# GNUBLIN-DIP-EASY_V100.net
KiCad netlist of a schematic drawn in EAGLE
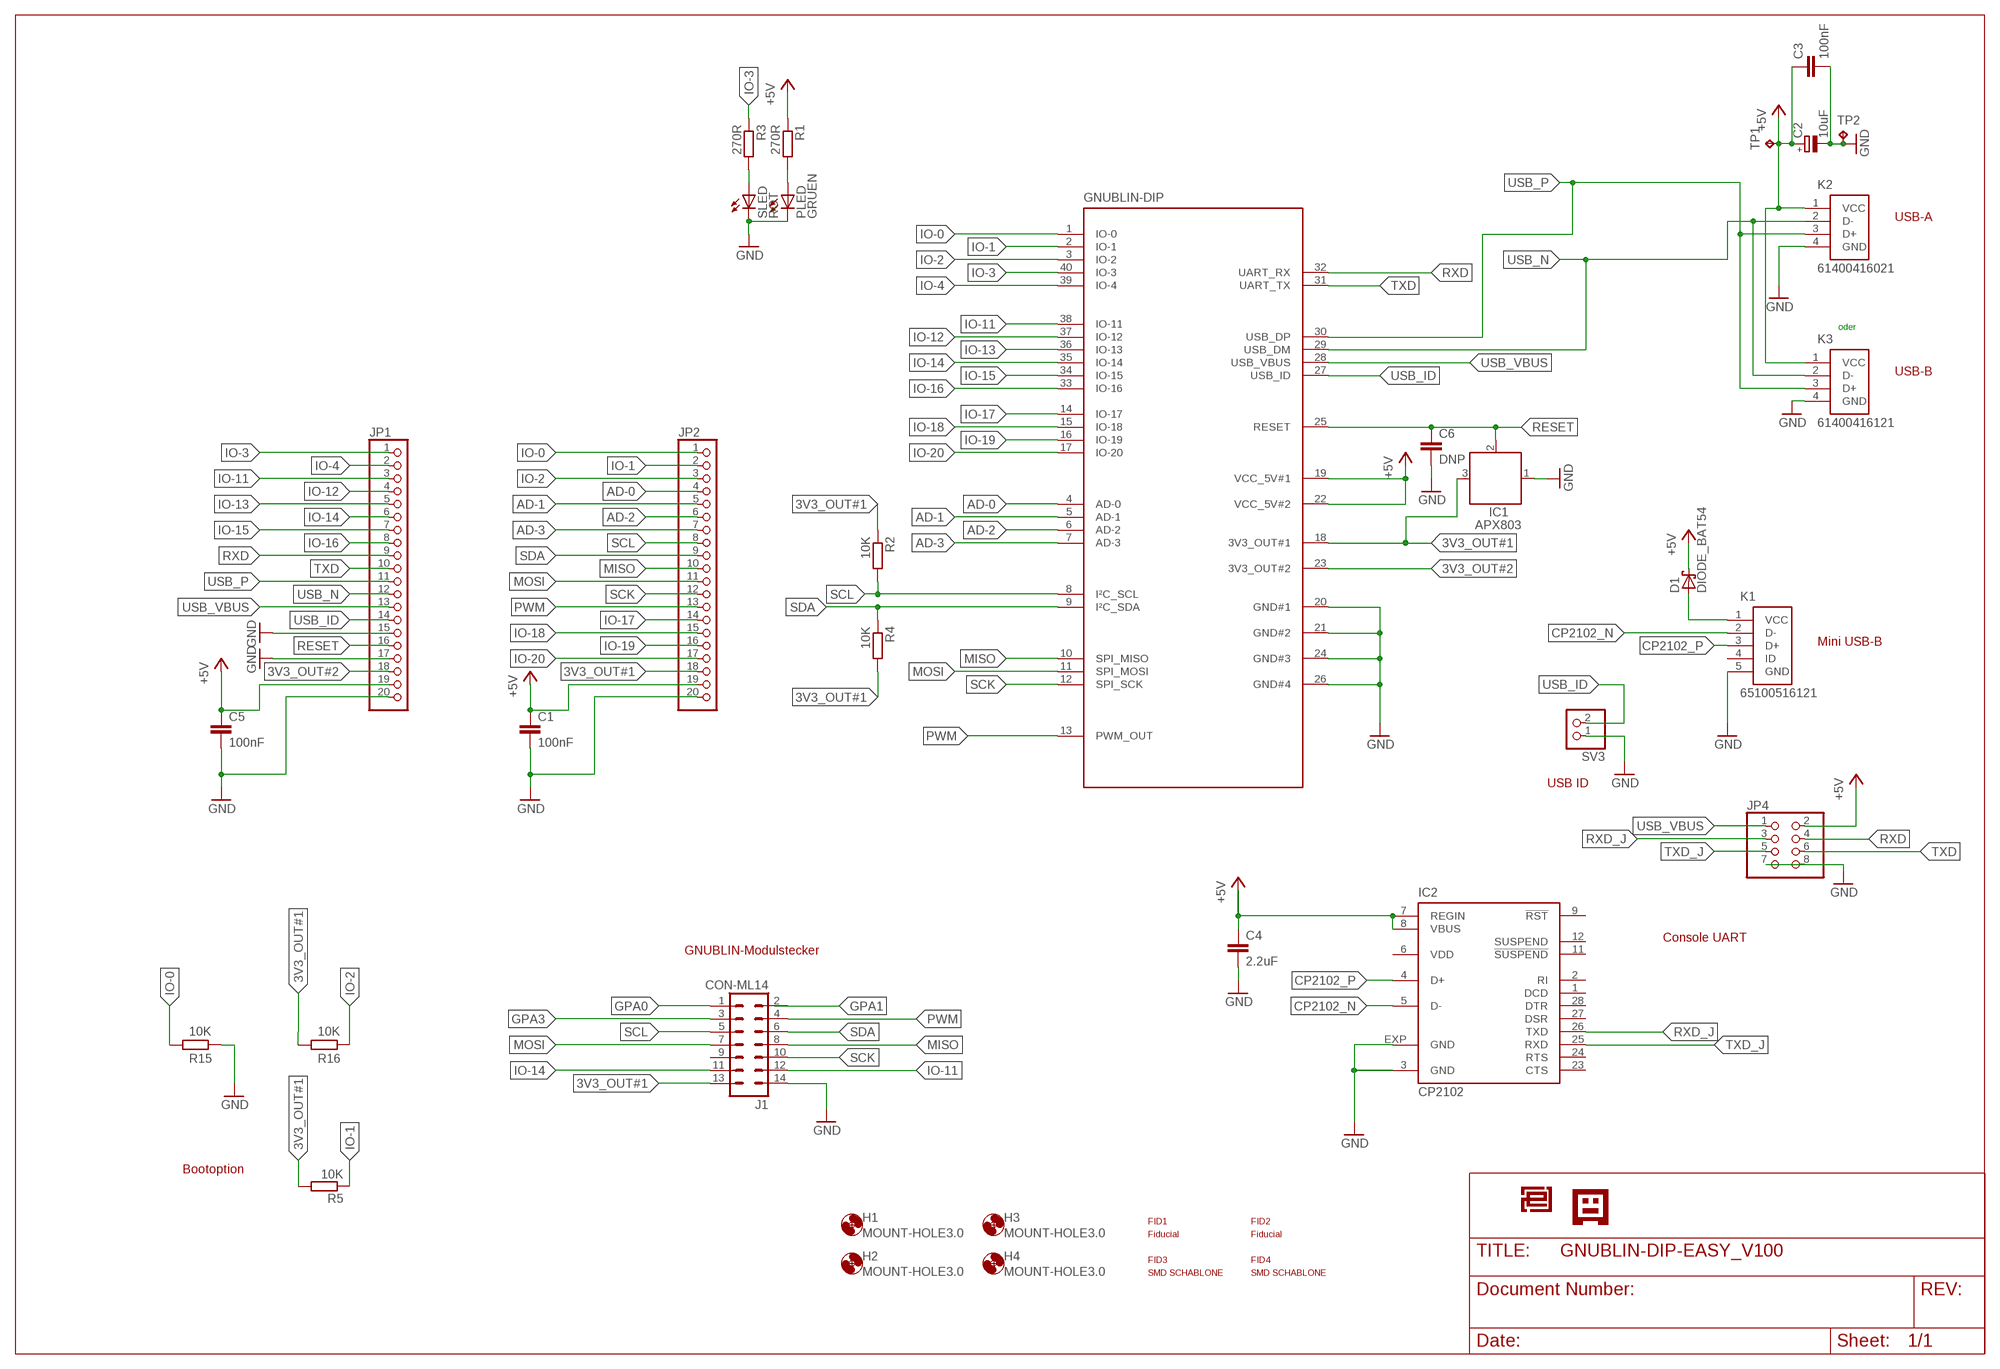
[diagram p0: schematic, sheet 1]

(export (version "E")
  (design (tool "Eeschema 10.0.6"))
  (components
    (comp (ref "C1")
      (value "100nF")
      (footprint "eagle-import:C0805")
      (libsource (lib "eagle-import") (part "C-EUC0805"))
    )
    (comp (ref "C2")
      (value "10uF")
      (footprint "eagle-import:D_7343-31R")
      (libsource (lib "eagle-import") (part "CPOL-EUD/7343-31R"))
    )
    (comp (ref "C3")
      (value "100nF")
      (footprint "eagle-import:C0805")
      (libsource (lib "eagle-import") (part "C-EUC0805"))
    )
    (comp (ref "C4")
      (value "2.2uF")
      (footprint "eagle-import:C0805")
      (libsource (lib "eagle-import") (part "C-EUC0805"))
    )
    (comp (ref "C5")
      (value "100nF")
      (footprint "eagle-import:C0805")
      (libsource (lib "eagle-import") (part "C-EUC0805"))
    )
    (comp (ref "C6")
      (value "DNP")
      (footprint "eagle-import:C0805")
      (libsource (lib "eagle-import") (part "C-EUC0805"))
    )
    (comp (ref "D1")
      (value "DIODE_BAT54")
      (footprint "eagle-import:SOT-23")
      (libsource (lib "eagle-import") (part "DIODE_BAT54"))
    )
    (comp (ref "FID1")
      (value "PASSERMARKEN_FIDUCIAL")
      (footprint "eagle-import:PASSERMARKEN_FIDUCIAL")
      (libsource (lib "eagle-import") (part "PASSERMARKEN_FIDUCIAL"))
    )
    (comp (ref "FID2")
      (value "PASSERMARKEN_FIDUCIAL")
      (footprint "eagle-import:PASSERMARKEN_FIDUCIAL")
      (libsource (lib "eagle-import") (part "PASSERMARKEN_FIDUCIAL"))
    )
    (comp (ref "FID3")
      (value "PASSERMARKEN_FIDUCIAL")
      (footprint "eagle-import:PASSERMARKEN_FIDUCIAL")
      (libsource (lib "eagle-import") (part "SMDSCHABLONE_PASSERMARKEN_FIDUCIAL"))
    )
    (comp (ref "FID4")
      (value "PASSERMARKEN_FIDUCIAL")
      (footprint "eagle-import:PASSERMARKEN_FIDUCIAL")
      (libsource (lib "eagle-import") (part "SMDSCHABLONE_PASSERMARKEN_FIDUCIAL"))
    )
    (comp (ref "H1")
      (value "MOUNT-HOLE3.0")
      (footprint "eagle-import:3,0")
      (libsource (lib "eagle-import") (part "MOUNT-HOLE3.0"))
    )
    (comp (ref "H2")
      (value "MOUNT-HOLE3.0")
      (footprint "eagle-import:3,0")
      (libsource (lib "eagle-import") (part "MOUNT-HOLE3.0"))
    )
    (comp (ref "H3")
      (value "MOUNT-HOLE3.0")
      (footprint "eagle-import:3,0")
      (libsource (lib "eagle-import") (part "MOUNT-HOLE3.0"))
    )
    (comp (ref "H4")
      (value "MOUNT-HOLE3.0")
      (footprint "eagle-import:3,0")
      (libsource (lib "eagle-import") (part "MOUNT-HOLE3.0"))
    )
    (comp (ref "IC1")
      (value "APX803")
      (footprint "eagle-import:SOT23")
      (libsource (lib "eagle-import") (part "APX803"))
    )
    (comp (ref "IC2")
      (value "CP2102")
      (footprint "eagle-import:MLP28")
      (fields (field (name "MF") "FARNELL") (field (name "MPN") "CP2102-GM"))
      (libsource (lib "eagle-import") (part "CP2102"))
    )
    (comp (ref "J1")
      (value "CON-ML14")
      (footprint "eagle-import:ML-14")
      (libsource (lib "eagle-import") (part "CON-ML14"))
    )
    (comp (ref "JP1")
      (value "PINHD-1X20")
      (footprint "eagle-import:1X20")
      (libsource (lib "eagle-import") (part "PINHD-1X20"))
    )
    (comp (ref "JP2")
      (value "PINHD-1X20")
      (footprint "eagle-import:1X20")
      (libsource (lib "eagle-import") (part "PINHD-1X20"))
    )
    (comp (ref "JP4")
      (value "PINHD-2X4")
      (footprint "eagle-import:2X04")
      (libsource (lib "eagle-import") (part "PINHD-2X4"))
    )
    (comp (ref "K1")
      (value "65100516121")
      (footprint "eagle-import:65100516121")
      (libsource (lib "eagle-import") (part "65100516121"))
    )
    (comp (ref "K2")
      (value "61400416021")
      (footprint "eagle-import:61400416021")
      (libsource (lib "eagle-import") (part "61400416021"))
    )
    (comp (ref "K3")
      (value "61400416121")
      (footprint "eagle-import:61400416121")
      (libsource (lib "eagle-import") (part "61400416121"))
    )
    (comp (ref "PLED")
      (value "GRUEN")
      (footprint "eagle-import:CHIPLED_0805")
      (libsource (lib "eagle-import") (part "LEDCHIPLED_0805"))
    )
    (comp (ref "R1")
      (value "270R")
      (footprint "eagle-import:R0805")
      (libsource (lib "eagle-import") (part "R-EU_R0805"))
    )
    (comp (ref "R2")
      (value "10K")
      (footprint "eagle-import:R0805")
      (libsource (lib "eagle-import") (part "R-EU_R0805"))
    )
    (comp (ref "R3")
      (value "270R")
      (footprint "eagle-import:R0805")
      (libsource (lib "eagle-import") (part "R-EU_R0805"))
    )
    (comp (ref "R4")
      (value "10K")
      (footprint "eagle-import:R0805")
      (libsource (lib "eagle-import") (part "R-EU_R0805"))
    )
    (comp (ref "R5")
      (value "10K")
      (footprint "eagle-import:R0805")
      (libsource (lib "eagle-import") (part "R-EU_R0805"))
    )
    (comp (ref "R15")
      (value "10K")
      (footprint "eagle-import:R0805")
      (libsource (lib "eagle-import") (part "R-EU_R0805"))
    )
    (comp (ref "R16")
      (value "10K")
      (footprint "eagle-import:R0805")
      (libsource (lib "eagle-import") (part "R-EU_R0805"))
    )
    (comp (ref "SLED")
      (value "ROT")
      (footprint "eagle-import:CHIPLED_0805")
      (libsource (lib "eagle-import") (part "LEDCHIPLED_0805"))
    )
    (comp (ref "SV3")
      (value "PINHD-1X2")
      (footprint "eagle-import:1X02")
      (libsource (lib "eagle-import") (part "PINHD-1X2"))
    )
    (comp (ref "TP1")
      (value "TPB1,27")
      (footprint "eagle-import:B1,27")
      (libsource (lib "eagle-import") (part "TPB1,27"))
    )
    (comp (ref "TP2")
      (value "TPB1,27")
      (footprint "eagle-import:B1,27")
      (libsource (lib "eagle-import") (part "TPB1,27"))
    )
    (comp (ref "U$1")
      (value "GNUBLIN-LOGODRUCK")
      (footprint "eagle-import:GNUBLINSIEBDRUCK")
      (libsource (lib "eagle-import") (part "GNUBLIN-LOGODRUCK"))
    )
    (comp (ref "U$2")
      (value "EPLOGOSIEB")
      (footprint "eagle-import:EPLOGOSIEBDRUCK")
      (libsource (lib "eagle-import") (part "EPLOGOSIEB"))
    )
    (comp (ref "U4")
      (value "GNUBLIN-DIP")
      (footprint "eagle-import:DIL40")
      (libsource (lib "eagle-import") (part "GNUBLIN-DIP"))
    )
  )
  (nets
    (net (code "1") (name "+5V") (class "Default")
      (node (ref "C1") (pin "1") (pinfunction "1_1") (pintype "passive"))
      (node (ref "C2") (pin "+") (pinfunction "+_+") (pintype "passive"))
      (node (ref "C3") (pin "1") (pinfunction "1_1") (pintype "passive"))
      (node (ref "C4") (pin "1") (pinfunction "1_1") (pintype "passive"))
      (node (ref "C5") (pin "1") (pinfunction "1_1") (pintype "passive"))
      (node (ref "D1") (pin "3") (pinfunction "C_3") (pintype "passive"))
      (node (ref "IC2") (pin "7") (pinfunction "REGIN_7") (pintype "passive"))
      (node (ref "IC2") (pin "8") (pinfunction "VBUS_8") (pintype "input"))
      (node (ref "JP1") (pin "19") (pinfunction "19_19") (pintype "passive"))
      (node (ref "JP2") (pin "19") (pinfunction "19_19") (pintype "passive"))
      (node (ref "JP4") (pin "2") (pinfunction "2_2") (pintype "passive"))
      (node (ref "K2") (pin "1") (pinfunction "VCC_1") (pintype "passive"))
      (node (ref "K3") (pin "1") (pinfunction "VCC_1") (pintype "passive"))
      (node (ref "R1") (pin "1") (pinfunction "1_1") (pintype "passive"))
      (node (ref "TP1") (pin "TP") (pinfunction "TP_TP") (pintype "input"))
      (node (ref "U4") (pin "19") (pinfunction "VCC_5V#1_19") (pintype "power_in"))
      (node (ref "U4") (pin "22") (pinfunction "VCC_5V#2_22") (pintype "power_in"))
    )
    (net (code "2") (name "/VDD") (class "Default")
      (node (ref "IC2") (pin "6") (pinfunction "VDD_6") (pintype "power_in"))
    )
    (net (code "3") (name "3V3_OUT#1") (class "Default")
      (node (ref "IC1") (pin "3") (pinfunction "VCC_3") (pintype "power_in"))
      (node (ref "J1") (pin "13") (pinfunction "13_13") (pintype "passive"))
      (node (ref "JP2") (pin "18") (pinfunction "18_18") (pintype "passive"))
      (node (ref "R16") (pin "1") (pinfunction "1_1") (pintype "passive"))
      (node (ref "R2") (pin "1") (pinfunction "1_1") (pintype "passive"))
      (node (ref "R4") (pin "2") (pinfunction "2_2") (pintype "passive"))
      (node (ref "R5") (pin "2") (pinfunction "2_2") (pintype "passive"))
      (node (ref "U4") (pin "18") (pinfunction "3V3_OUT#1_18") (pintype "power_in"))
    )
    (net (code "4") (name "3V3_OUT#2") (class "Default")
      (node (ref "JP1") (pin "18") (pinfunction "18_18") (pintype "passive"))
      (node (ref "U4") (pin "23") (pinfunction "3V3_OUT#2_23") (pintype "power_in"))
    )
    (net (code "5") (name "AD-0") (class "Default")
      (node (ref "JP2") (pin "4") (pinfunction "4_4") (pintype "passive"))
      (node (ref "U4") (pin "4") (pinfunction "AD-0_4") (pintype "input"))
    )
    (net (code "6") (name "AD-1") (class "Default")
      (node (ref "JP2") (pin "5") (pinfunction "5_5") (pintype "passive"))
      (node (ref "U4") (pin "5") (pinfunction "AD-1_5") (pintype "input"))
    )
    (net (code "7") (name "AD-2") (class "Default")
      (node (ref "JP2") (pin "6") (pinfunction "6_6") (pintype "passive"))
      (node (ref "U4") (pin "6") (pinfunction "AD-2_6") (pintype "input"))
    )
    (net (code "8") (name "AD-3") (class "Default")
      (node (ref "JP2") (pin "7") (pinfunction "7_7") (pintype "passive"))
      (node (ref "U4") (pin "7") (pinfunction "AD-3_7") (pintype "input"))
    )
    (net (code "9") (name "CP2102_N") (class "Default")
      (node (ref "IC2") (pin "5") (pinfunction "D-_5") (pintype "bidirectional"))
      (node (ref "K1") (pin "2") (pinfunction "D-_2") (pintype "passive"))
    )
    (net (code "10") (name "CP2102_P") (class "Default")
      (node (ref "IC2") (pin "4") (pinfunction "D+_4") (pintype "bidirectional"))
      (node (ref "K1") (pin "3") (pinfunction "D+_3") (pintype "passive"))
    )
    (net (code "11") (name "GND") (class "Default")
      (node (ref "C1") (pin "2") (pinfunction "2_2") (pintype "passive"))
      (node (ref "C2") (pin "-") (pinfunction "-_-") (pintype "passive"))
      (node (ref "C3") (pin "2") (pinfunction "2_2") (pintype "passive"))
      (node (ref "C4") (pin "2") (pinfunction "2_2") (pintype "passive"))
      (node (ref "C5") (pin "2") (pinfunction "2_2") (pintype "passive"))
      (node (ref "C6") (pin "2") (pinfunction "2_2") (pintype "passive"))
      (node (ref "IC1") (pin "1") (pinfunction "GND_1") (pintype "power_in"))
      (node (ref "IC2") (pin "3") (pinfunction "GND_3") (pintype "power_in"))
      (node (ref "IC2") (pin "EXP") (pinfunction "GND_EXP") (pintype "bidirectional"))
      (node (ref "J1") (pin "14") (pinfunction "14_14") (pintype "passive"))
      (node (ref "JP1") (pin "15") (pinfunction "15_15") (pintype "passive"))
      (node (ref "JP1") (pin "17") (pinfunction "17_17") (pintype "passive"))
      (node (ref "JP1") (pin "20") (pinfunction "20_20") (pintype "passive"))
      (node (ref "JP2") (pin "20") (pinfunction "20_20") (pintype "passive"))
      (node (ref "JP4") (pin "7") (pinfunction "7_7") (pintype "passive"))
      (node (ref "JP4") (pin "8") (pinfunction "8_8") (pintype "passive"))
      (node (ref "K1") (pin "5") (pinfunction "GND_5") (pintype "passive"))
      (node (ref "K2") (pin "4") (pinfunction "GND_4") (pintype "passive"))
      (node (ref "K3") (pin "4") (pinfunction "GND_4") (pintype "passive"))
      (node (ref "PLED") (pin "C") (pinfunction "C_C") (pintype "passive"))
      (node (ref "R15") (pin "2") (pinfunction "2_2") (pintype "passive"))
      (node (ref "SLED") (pin "C") (pinfunction "C_C") (pintype "passive"))
      (node (ref "SV3") (pin "1") (pinfunction "1_1") (pintype "passive"))
      (node (ref "TP2") (pin "TP") (pinfunction "TP_TP") (pintype "input"))
      (node (ref "U4") (pin "20") (pinfunction "GND#1_20") (pintype "power_in"))
      (node (ref "U4") (pin "21") (pinfunction "GND#2_21") (pintype "power_in"))
      (node (ref "U4") (pin "24") (pinfunction "GND#3_24") (pintype "power_in"))
      (node (ref "U4") (pin "26") (pinfunction "GND#4_26") (pintype "power_in"))
    )
    (net (code "12") (name "GPA0") (class "Default")
      (node (ref "J1") (pin "1") (pinfunction "1_1") (pintype "passive"))
    )
    (net (code "14") (name "GPA3") (class "Default")
      (node (ref "J1") (pin "3") (pinfunction "3_3") (pintype "passive"))
    )
    (net (code "15") (name "IO-0") (class "Default")
      (node (ref "JP2") (pin "1") (pinfunction "1_1") (pintype "passive"))
      (node (ref "R15") (pin "1") (pinfunction "1_1") (pintype "passive"))
      (node (ref "U4") (pin "1") (pinfunction "IO-0_1") (pintype "bidirectional"))
    )
    (net (code "16") (name "IO-1") (class "Default")
      (node (ref "JP2") (pin "2") (pinfunction "2_2") (pintype "passive"))
      (node (ref "R5") (pin "1") (pinfunction "1_1") (pintype "passive"))
      (node (ref "U4") (pin "2") (pinfunction "IO-1_2") (pintype "bidirectional"))
    )
    (net (code "17") (name "IO-2") (class "Default")
      (node (ref "JP2") (pin "3") (pinfunction "3_3") (pintype "passive"))
      (node (ref "R16") (pin "2") (pinfunction "2_2") (pintype "passive"))
      (node (ref "U4") (pin "3") (pinfunction "IO-2_3") (pintype "bidirectional"))
    )
    (net (code "18") (name "IO-3") (class "Default")
      (node (ref "JP1") (pin "1") (pinfunction "1_1") (pintype "passive"))
      (node (ref "R3") (pin "1") (pinfunction "1_1") (pintype "passive"))
      (node (ref "U4") (pin "40") (pinfunction "IO-3_40") (pintype "bidirectional"))
    )
    (net (code "19") (name "IO-4") (class "Default")
      (node (ref "JP1") (pin "2") (pinfunction "2_2") (pintype "passive"))
      (node (ref "U4") (pin "39") (pinfunction "IO-4_39") (pintype "bidirectional"))
    )
    (net (code "20") (name "IO-11") (class "Default")
      (node (ref "J1") (pin "12") (pinfunction "12_12") (pintype "passive"))
      (node (ref "JP1") (pin "3") (pinfunction "3_3") (pintype "passive"))
      (node (ref "U4") (pin "38") (pinfunction "IO-11_38") (pintype "bidirectional"))
    )
    (net (code "21") (name "IO-12") (class "Default")
      (node (ref "JP1") (pin "4") (pinfunction "4_4") (pintype "passive"))
      (node (ref "U4") (pin "37") (pinfunction "IO-12_37") (pintype "bidirectional"))
    )
    (net (code "22") (name "IO-13") (class "Default")
      (node (ref "JP1") (pin "5") (pinfunction "5_5") (pintype "passive"))
      (node (ref "U4") (pin "36") (pinfunction "IO-13_36") (pintype "bidirectional"))
    )
    (net (code "23") (name "IO-14") (class "Default")
      (node (ref "J1") (pin "11") (pinfunction "11_11") (pintype "passive"))
      (node (ref "JP1") (pin "6") (pinfunction "6_6") (pintype "passive"))
      (node (ref "U4") (pin "35") (pinfunction "IO-14_35") (pintype "bidirectional"))
    )
    (net (code "24") (name "IO-15") (class "Default")
      (node (ref "JP1") (pin "7") (pinfunction "7_7") (pintype "passive"))
      (node (ref "U4") (pin "34") (pinfunction "IO-15_34") (pintype "bidirectional"))
    )
    (net (code "25") (name "IO-16") (class "Default")
      (node (ref "JP1") (pin "8") (pinfunction "8_8") (pintype "passive"))
      (node (ref "U4") (pin "33") (pinfunction "IO-16_33") (pintype "bidirectional"))
    )
    (net (code "26") (name "IO-17") (class "Default")
      (node (ref "JP2") (pin "14") (pinfunction "14_14") (pintype "passive"))
      (node (ref "U4") (pin "14") (pinfunction "IO-17_14") (pintype "bidirectional"))
    )
    (net (code "27") (name "IO-18") (class "Default")
      (node (ref "JP2") (pin "15") (pinfunction "15_15") (pintype "passive"))
      (node (ref "U4") (pin "15") (pinfunction "IO-18_15") (pintype "bidirectional"))
    )
    (net (code "28") (name "IO-19") (class "Default")
      (node (ref "JP2") (pin "16") (pinfunction "16_16") (pintype "passive"))
      (node (ref "U4") (pin "16") (pinfunction "IO-19_16") (pintype "bidirectional"))
    )
    (net (code "29") (name "IO-20") (class "Default")
      (node (ref "JP2") (pin "17") (pinfunction "17_17") (pintype "passive"))
      (node (ref "U4") (pin "17") (pinfunction "IO-20_17") (pintype "bidirectional"))
    )
    (net (code "30") (name "MISO") (class "Default")
      (node (ref "J1") (pin "8") (pinfunction "8_8") (pintype "passive"))
      (node (ref "JP2") (pin "10") (pinfunction "10_10") (pintype "passive"))
      (node (ref "U4") (pin "10") (pinfunction "SPI_MISO_10") (pintype "bidirectional"))
    )
    (net (code "31") (name "MOSI") (class "Default")
      (node (ref "J1") (pin "7") (pinfunction "7_7") (pintype "passive"))
      (node (ref "JP2") (pin "11") (pinfunction "11_11") (pintype "passive"))
      (node (ref "U4") (pin "11") (pinfunction "SPI_MOSI_11") (pintype "bidirectional"))
    )
    (net (code "32") (name "Net-(D1-A)") (class "Default")
      (node (ref "D1") (pin "1") (pinfunction "A_1") (pintype "passive"))
      (node (ref "K1") (pin "1") (pinfunction "VCC_1") (pintype "passive"))
    )
    (net (code "33") (name "Net-(PLED-PadA)") (class "Default")
      (node (ref "PLED") (pin "A") (pinfunction "A_A") (pintype "passive"))
      (node (ref "R1") (pin "2") (pinfunction "2_2") (pintype "passive"))
    )
    (net (code "34") (name "Net-(R3-Pad2)") (class "Default")
      (node (ref "R3") (pin "2") (pinfunction "2_2") (pintype "passive"))
      (node (ref "SLED") (pin "A") (pinfunction "A_A") (pintype "passive"))
    )
    (net (code "35") (name "PWM") (class "Default")
      (node (ref "J1") (pin "4") (pinfunction "4_4") (pintype "passive"))
      (node (ref "JP2") (pin "13") (pinfunction "13_13") (pintype "passive"))
      (node (ref "U4") (pin "13") (pinfunction "PWM_OUT_13") (pintype "output"))
    )
    (net (code "36") (name "RESET") (class "Default")
      (node (ref "C6") (pin "1") (pinfunction "1_1") (pintype "passive"))
      (node (ref "IC1") (pin "2") (pinfunction "~{RESET}_2") (pintype "output"))
      (node (ref "JP1") (pin "16") (pinfunction "16_16") (pintype "passive"))
      (node (ref "U4") (pin "25") (pinfunction "RESET_25") (pintype "input"))
    )
    (net (code "37") (name "RXD") (class "Default")
      (node (ref "JP1") (pin "9") (pinfunction "9_9") (pintype "passive"))
      (node (ref "JP4") (pin "4") (pinfunction "4_4") (pintype "passive"))
      (node (ref "U4") (pin "32") (pinfunction "UART_RX_32") (pintype "input"))
    )
    (net (code "38") (name "RXD_J") (class "Default")
      (node (ref "IC2") (pin "26") (pinfunction "TXD_26") (pintype "output"))
      (node (ref "JP4") (pin "3") (pinfunction "3_3") (pintype "passive"))
    )
    (net (code "39") (name "SCK") (class "Default")
      (node (ref "J1") (pin "10") (pinfunction "10_10") (pintype "passive"))
      (node (ref "JP2") (pin "12") (pinfunction "12_12") (pintype "passive"))
      (node (ref "U4") (pin "12") (pinfunction "SPI_SCK_12") (pintype "bidirectional"))
    )
    (net (code "40") (name "SCL") (class "Default")
      (node (ref "J1") (pin "5") (pinfunction "5_5") (pintype "passive"))
      (node (ref "JP2") (pin "8") (pinfunction "8_8") (pintype "passive"))
      (node (ref "R2") (pin "2") (pinfunction "2_2") (pintype "passive"))
      (node (ref "U4") (pin "8") (pinfunction "I²C_SCL_8") (pintype "bidirectional"))
    )
    (net (code "41") (name "SDA") (class "Default")
      (node (ref "J1") (pin "6") (pinfunction "6_6") (pintype "passive"))
      (node (ref "JP2") (pin "9") (pinfunction "9_9") (pintype "passive"))
      (node (ref "R4") (pin "1") (pinfunction "1_1") (pintype "passive"))
      (node (ref "U4") (pin "9") (pinfunction "I²C_SDA_9") (pintype "bidirectional"))
    )
    (net (code "42") (name "TXD") (class "Default")
      (node (ref "JP1") (pin "10") (pinfunction "10_10") (pintype "passive"))
      (node (ref "JP4") (pin "6") (pinfunction "6_6") (pintype "passive"))
      (node (ref "U4") (pin "31") (pinfunction "UART_TX_31") (pintype "output"))
    )
    (net (code "43") (name "TXD_J") (class "Default")
      (node (ref "IC2") (pin "25") (pinfunction "RXD_25") (pintype "input"))
      (node (ref "JP4") (pin "5") (pinfunction "5_5") (pintype "passive"))
    )
    (net (code "44") (name "USB_ID") (class "Default")
      (node (ref "JP1") (pin "14") (pinfunction "14_14") (pintype "passive"))
      (node (ref "SV3") (pin "2") (pinfunction "2_2") (pintype "passive"))
      (node (ref "U4") (pin "27") (pinfunction "USB_ID_27") (pintype "bidirectional"))
    )
    (net (code "45") (name "USB_N") (class "Default")
      (node (ref "JP1") (pin "12") (pinfunction "12_12") (pintype "passive"))
      (node (ref "K2") (pin "2") (pinfunction "D-_2") (pintype "passive"))
      (node (ref "K3") (pin "2") (pinfunction "D-_2") (pintype "passive"))
      (node (ref "U4") (pin "29") (pinfunction "USB_DM_29") (pintype "bidirectional"))
    )
    (net (code "46") (name "USB_P") (class "Default")
      (node (ref "JP1") (pin "11") (pinfunction "11_11") (pintype "passive"))
      (node (ref "K2") (pin "3") (pinfunction "D+_3") (pintype "passive"))
      (node (ref "K3") (pin "3") (pinfunction "D+_3") (pintype "passive"))
      (node (ref "U4") (pin "30") (pinfunction "USB_DP_30") (pintype "bidirectional"))
    )
    (net (code "47") (name "USB_VBUS") (class "Default")
      (node (ref "JP1") (pin "13") (pinfunction "13_13") (pintype "passive"))
      (node (ref "JP4") (pin "1") (pinfunction "1_1") (pintype "passive"))
      (node (ref "U4") (pin "28") (pinfunction "USB_VBUS_28") (pintype "bidirectional"))
    )
    (net (code "48") (name "unconnected-(IC2-CTS-Pad23)") (class "Default")
      (node (ref "IC2") (pin "23") (pinfunction "CTS_23") (pintype "input"))
    )
    (net (code "49") (name "unconnected-(IC2-DCD-Pad1)") (class "Default")
      (node (ref "IC2") (pin "1") (pinfunction "DCD_1") (pintype "input"))
    )
    (net (code "50") (name "unconnected-(IC2-DSR-Pad27)") (class "Default")
      (node (ref "IC2") (pin "27") (pinfunction "DSR_27") (pintype "input"))
    )
    (net (code "51") (name "unconnected-(IC2-DTR-Pad28)") (class "Default")
      (node (ref "IC2") (pin "28") (pinfunction "DTR_28") (pintype "output"))
    )
    (net (code "52") (name "unconnected-(IC2-RI-Pad2)") (class "Default")
      (node (ref "IC2") (pin "2") (pinfunction "RI_2") (pintype "input"))
    )
    (net (code "53") (name "unconnected-(IC2-RTS-Pad24)") (class "Default")
      (node (ref "IC2") (pin "24") (pinfunction "RTS_24") (pintype "output"))
    )
    (net (code "54") (name "unconnected-(IC2-SUSPEND-Pad12)") (class "Default")
      (node (ref "IC2") (pin "12") (pinfunction "SUSPEND_12") (pintype "output"))
    )
    (net (code "55") (name "unconnected-(IC2-~{RST}-Pad9)") (class "Default")
      (node (ref "IC2") (pin "9") (pinfunction "~{RST}_9") (pintype "bidirectional"))
    )
    (net (code "56") (name "unconnected-(IC2-~{SUSPEND}-Pad11)") (class "Default")
      (node (ref "IC2") (pin "11") (pinfunction "~{SUSPEND}_11") (pintype "output"))
    )
    (net (code "57") (name "unconnected-(J1-Pad2)") (class "Default")
      (node (ref "J1") (pin "2") (pinfunction "2_2") (pintype "passive"))
    )
    (net (code "58") (name "unconnected-(J1-Pad9)") (class "Default")
      (node (ref "J1") (pin "9") (pinfunction "9_9") (pintype "passive"))
    )
    (net (code "59") (name "unconnected-(K1-ID-Pad4)") (class "Default")
      (node (ref "K1") (pin "4") (pinfunction "ID_4") (pintype "passive"))
    )
  )
)
